# NRF52840_UFO.net
KiCad netlist of a schematic drawn in Altium Designer
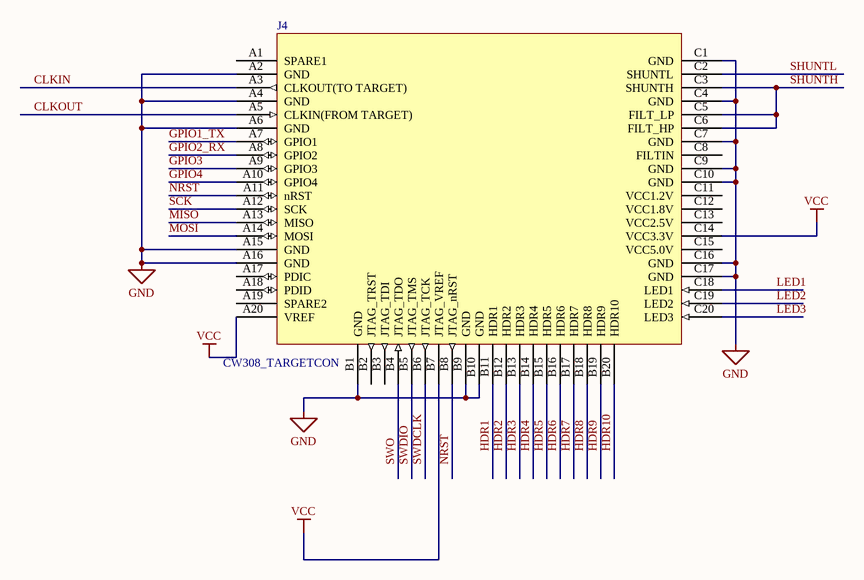
[diagram p0: NRF52840_UFO.SchDoc]

(export (version "E")
  (design (tool "Eeschema 10.0.6"))
  (components
    (comp (ref "J4")
      (value "CW308_TARGETCON")
      (footprint "CW308_TBOARD_CONN")
      (description "CW308 \"Standard\" Target Board Connector")
      (fields (field (name "PART NUMBER") "CW308_TBOARD"))
      (libsource (lib "NewAE_AltiumLib") (part "CW308_TBOARD"))
    )
  )
  (nets
    (net (code "1") (name "/CLKIN") (class "Default")
      (node (ref "J4") (pin "A3") (pinfunction "CLKOUT(TO_TARGET)_A3") (pintype "output"))
    )
    (net (code "2") (name "/CLKOUT") (class "Default")
      (node (ref "J4") (pin "A5") (pinfunction "CLKIN(FROM_TARGET)_A5") (pintype "input"))
    )
    (net (code "3") (name "/GPIO1_TX") (class "Default")
      (node (ref "J4") (pin "A7") (pinfunction "GPIO1_A7") (pintype "bidirectional"))
    )
    (net (code "4") (name "/GPIO2_RX") (class "Default")
      (node (ref "J4") (pin "A8") (pinfunction "GPIO2_A8") (pintype "bidirectional"))
    )
    (net (code "5") (name "/GPIO3") (class "Default")
      (node (ref "J4") (pin "A9") (pinfunction "GPIO3_A9") (pintype "bidirectional"))
    )
    (net (code "6") (name "/GPIO4") (class "Default")
      (node (ref "J4") (pin "A10") (pinfunction "GPIO4_A10") (pintype "bidirectional"))
    )
    (net (code "7") (name "/HDR1") (class "Default")
      (node (ref "J4") (pin "B11") (pinfunction "HDR1_B11") (pintype "passive"))
    )
    (net (code "8") (name "/HDR2") (class "Default")
      (node (ref "J4") (pin "B12") (pinfunction "HDR2_B12") (pintype "passive"))
    )
    (net (code "9") (name "/HDR3") (class "Default")
      (node (ref "J4") (pin "B13") (pinfunction "HDR3_B13") (pintype "passive"))
    )
    (net (code "10") (name "/HDR4") (class "Default")
      (node (ref "J4") (pin "B14") (pinfunction "HDR4_B14") (pintype "passive"))
    )
    (net (code "11") (name "/HDR5") (class "Default")
      (node (ref "J4") (pin "B15") (pinfunction "HDR5_B15") (pintype "passive"))
    )
    (net (code "12") (name "/HDR6") (class "Default")
      (node (ref "J4") (pin "B16") (pinfunction "HDR6_B16") (pintype "passive"))
    )
    (net (code "13") (name "/HDR7") (class "Default")
      (node (ref "J4") (pin "B17") (pinfunction "HDR7_B17") (pintype "passive"))
    )
    (net (code "14") (name "/HDR8") (class "Default")
      (node (ref "J4") (pin "B18") (pinfunction "HDR8_B18") (pintype "passive"))
    )
    (net (code "15") (name "/HDR9") (class "Default")
      (node (ref "J4") (pin "B19") (pinfunction "HDR9_B19") (pintype "passive"))
    )
    (net (code "16") (name "/HDR10") (class "Default")
      (node (ref "J4") (pin "B20") (pinfunction "HDR10_B20") (pintype "passive"))
    )
    (net (code "17") (name "/LED1") (class "Default")
      (node (ref "J4") (pin "C18") (pinfunction "LED1_C18") (pintype "input"))
    )
    (net (code "18") (name "/LED2") (class "Default")
      (node (ref "J4") (pin "C19") (pinfunction "LED2_C19") (pintype "input"))
    )
    (net (code "19") (name "/LED3") (class "Default")
      (node (ref "J4") (pin "C20") (pinfunction "LED3_C20") (pintype "input"))
    )
    (net (code "20") (name "/MISO") (class "Default")
      (node (ref "J4") (pin "A13") (pinfunction "MISO_A13") (pintype "bidirectional"))
    )
    (net (code "21") (name "/MOSI") (class "Default")
      (node (ref "J4") (pin "A14") (pinfunction "MOSI_A14") (pintype "bidirectional"))
    )
    (net (code "22") (name "/NRST") (class "Default")
      (node (ref "J4") (pin "A11") (pinfunction "nRST_A11") (pintype "bidirectional"))
      (node (ref "J4") (pin "B8") (pinfunction "JTAG_nRST_B8") (pintype "output"))
    )
    (net (code "23") (name "/SCK") (class "Default")
      (node (ref "J4") (pin "A12") (pinfunction "SCK_A12") (pintype "bidirectional"))
    )
    (net (code "24") (name "/SHUNTH") (class "Default")
      (node (ref "J4") (pin "C3") (pinfunction "SHUNTH_C3") (pintype "passive"))
      (node (ref "J4") (pin "C5") (pinfunction "FILT_LP_C5") (pintype "passive"))
      (node (ref "J4") (pin "C6") (pinfunction "FILT_HP_C6") (pintype "passive"))
    )
    (net (code "25") (name "/SHUNTL") (class "Default")
      (node (ref "J4") (pin "C2") (pinfunction "SHUNTL_C2") (pintype "passive"))
    )
    (net (code "26") (name "/SWDCLK") (class "Default")
      (node (ref "J4") (pin "B6") (pinfunction "JTAG_TCK_B6") (pintype "output"))
    )
    (net (code "27") (name "/SWDIO") (class "Default")
      (node (ref "J4") (pin "B5") (pinfunction "JTAG_TMS_B5") (pintype "output"))
    )
    (net (code "28") (name "/SWO") (class "Default")
      (node (ref "J4") (pin "B4") (pinfunction "JTAG_TDO_B4") (pintype "input"))
    )
    (net (code "29") (name "GND") (class "Default")
      (node (ref "J4") (pin "A15") (pinfunction "GND_A15") (pintype "passive"))
      (node (ref "J4") (pin "A16") (pinfunction "GND_A16") (pintype "passive"))
      (node (ref "J4") (pin "A2") (pinfunction "GND_A2") (pintype "passive"))
      (node (ref "J4") (pin "A4") (pinfunction "GND_A4") (pintype "passive"))
      (node (ref "J4") (pin "A6") (pinfunction "GND_A6") (pintype "power_in"))
      (node (ref "J4") (pin "B1") (pinfunction "GND_B1") (pintype "passive"))
      (node (ref "J4") (pin "B10") (pinfunction "GND_B10") (pintype "passive"))
      (node (ref "J4") (pin "B9") (pinfunction "GND_B9") (pintype "passive"))
      (node (ref "J4") (pin "C1") (pinfunction "GND_C1") (pintype "power_in"))
      (node (ref "J4") (pin "C10") (pinfunction "GND_C10") (pintype "power_in"))
      (node (ref "J4") (pin "C16") (pinfunction "GND_C16") (pintype "power_in"))
      (node (ref "J4") (pin "C17") (pinfunction "GND_C17") (pintype "power_in"))
      (node (ref "J4") (pin "C4") (pinfunction "GND_C4") (pintype "power_in"))
      (node (ref "J4") (pin "C7") (pinfunction "GND_C7") (pintype "power_in"))
      (node (ref "J4") (pin "C9") (pinfunction "GND_C9") (pintype "power_in"))
    )
    (net (code "30") (name "VCC") (class "Default")
      (node (ref "J4") (pin "A20") (pinfunction "VREF_A20") (pintype "tri_state"))
      (node (ref "J4") (pin "B7") (pinfunction "JTAG_VREF_B7") (pintype "tri_state"))
      (node (ref "J4") (pin "C14") (pinfunction "VCC3.3V_C14") (pintype "power_in"))
    )
    (net (code "31") (name "unconnected-(J4-FILTIN-PadC8)") (class "Default")
      (node (ref "J4") (pin "C8") (pinfunction "FILTIN_C8") (pintype "passive"))
    )
    (net (code "32") (name "unconnected-(J4-JTAG_TDI-PadB3)") (class "Default")
      (node (ref "J4") (pin "B3") (pinfunction "JTAG_TDI_B3") (pintype "output"))
    )
    (net (code "33") (name "unconnected-(J4-JTAG_TRST-PadB2)") (class "Default")
      (node (ref "J4") (pin "B2") (pinfunction "JTAG_TRST_B2") (pintype "output"))
    )
    (net (code "34") (name "unconnected-(J4-PDIC-PadA17)") (class "Default")
      (node (ref "J4") (pin "A17") (pinfunction "PDIC_A17") (pintype "bidirectional"))
    )
    (net (code "35") (name "unconnected-(J4-PDID-PadA18)") (class "Default")
      (node (ref "J4") (pin "A18") (pinfunction "PDID_A18") (pintype "bidirectional"))
    )
    (net (code "36") (name "unconnected-(J4-SPARE1-PadA1)") (class "Default")
      (node (ref "J4") (pin "A1") (pinfunction "SPARE1_A1") (pintype "passive"))
    )
    (net (code "37") (name "unconnected-(J4-SPARE2-PadA19)") (class "Default")
      (node (ref "J4") (pin "A19") (pinfunction "SPARE2_A19") (pintype "passive"))
    )
    (net (code "38") (name "unconnected-(J4-VCC1.2V-PadC11)") (class "Default")
      (node (ref "J4") (pin "C11") (pinfunction "VCC1.2V_C11") (pintype "power_in"))
    )
    (net (code "39") (name "unconnected-(J4-VCC1.8V-PadC12)") (class "Default")
      (node (ref "J4") (pin "C12") (pinfunction "VCC1.8V_C12") (pintype "power_in"))
    )
    (net (code "40") (name "unconnected-(J4-VCC2.5V-PadC13)") (class "Default")
      (node (ref "J4") (pin "C13") (pinfunction "VCC2.5V_C13") (pintype "power_in"))
    )
    (net (code "41") (name "unconnected-(J4-VCC5.0V-PadC15)") (class "Default")
      (node (ref "J4") (pin "C15") (pinfunction "VCC5.0V_C15") (pintype "power_in"))
    )
  )
)
